# 2_waffling60-MXHS-ISO_matrix.net
KiCad netlist of a schematic drawn in Altium Designer
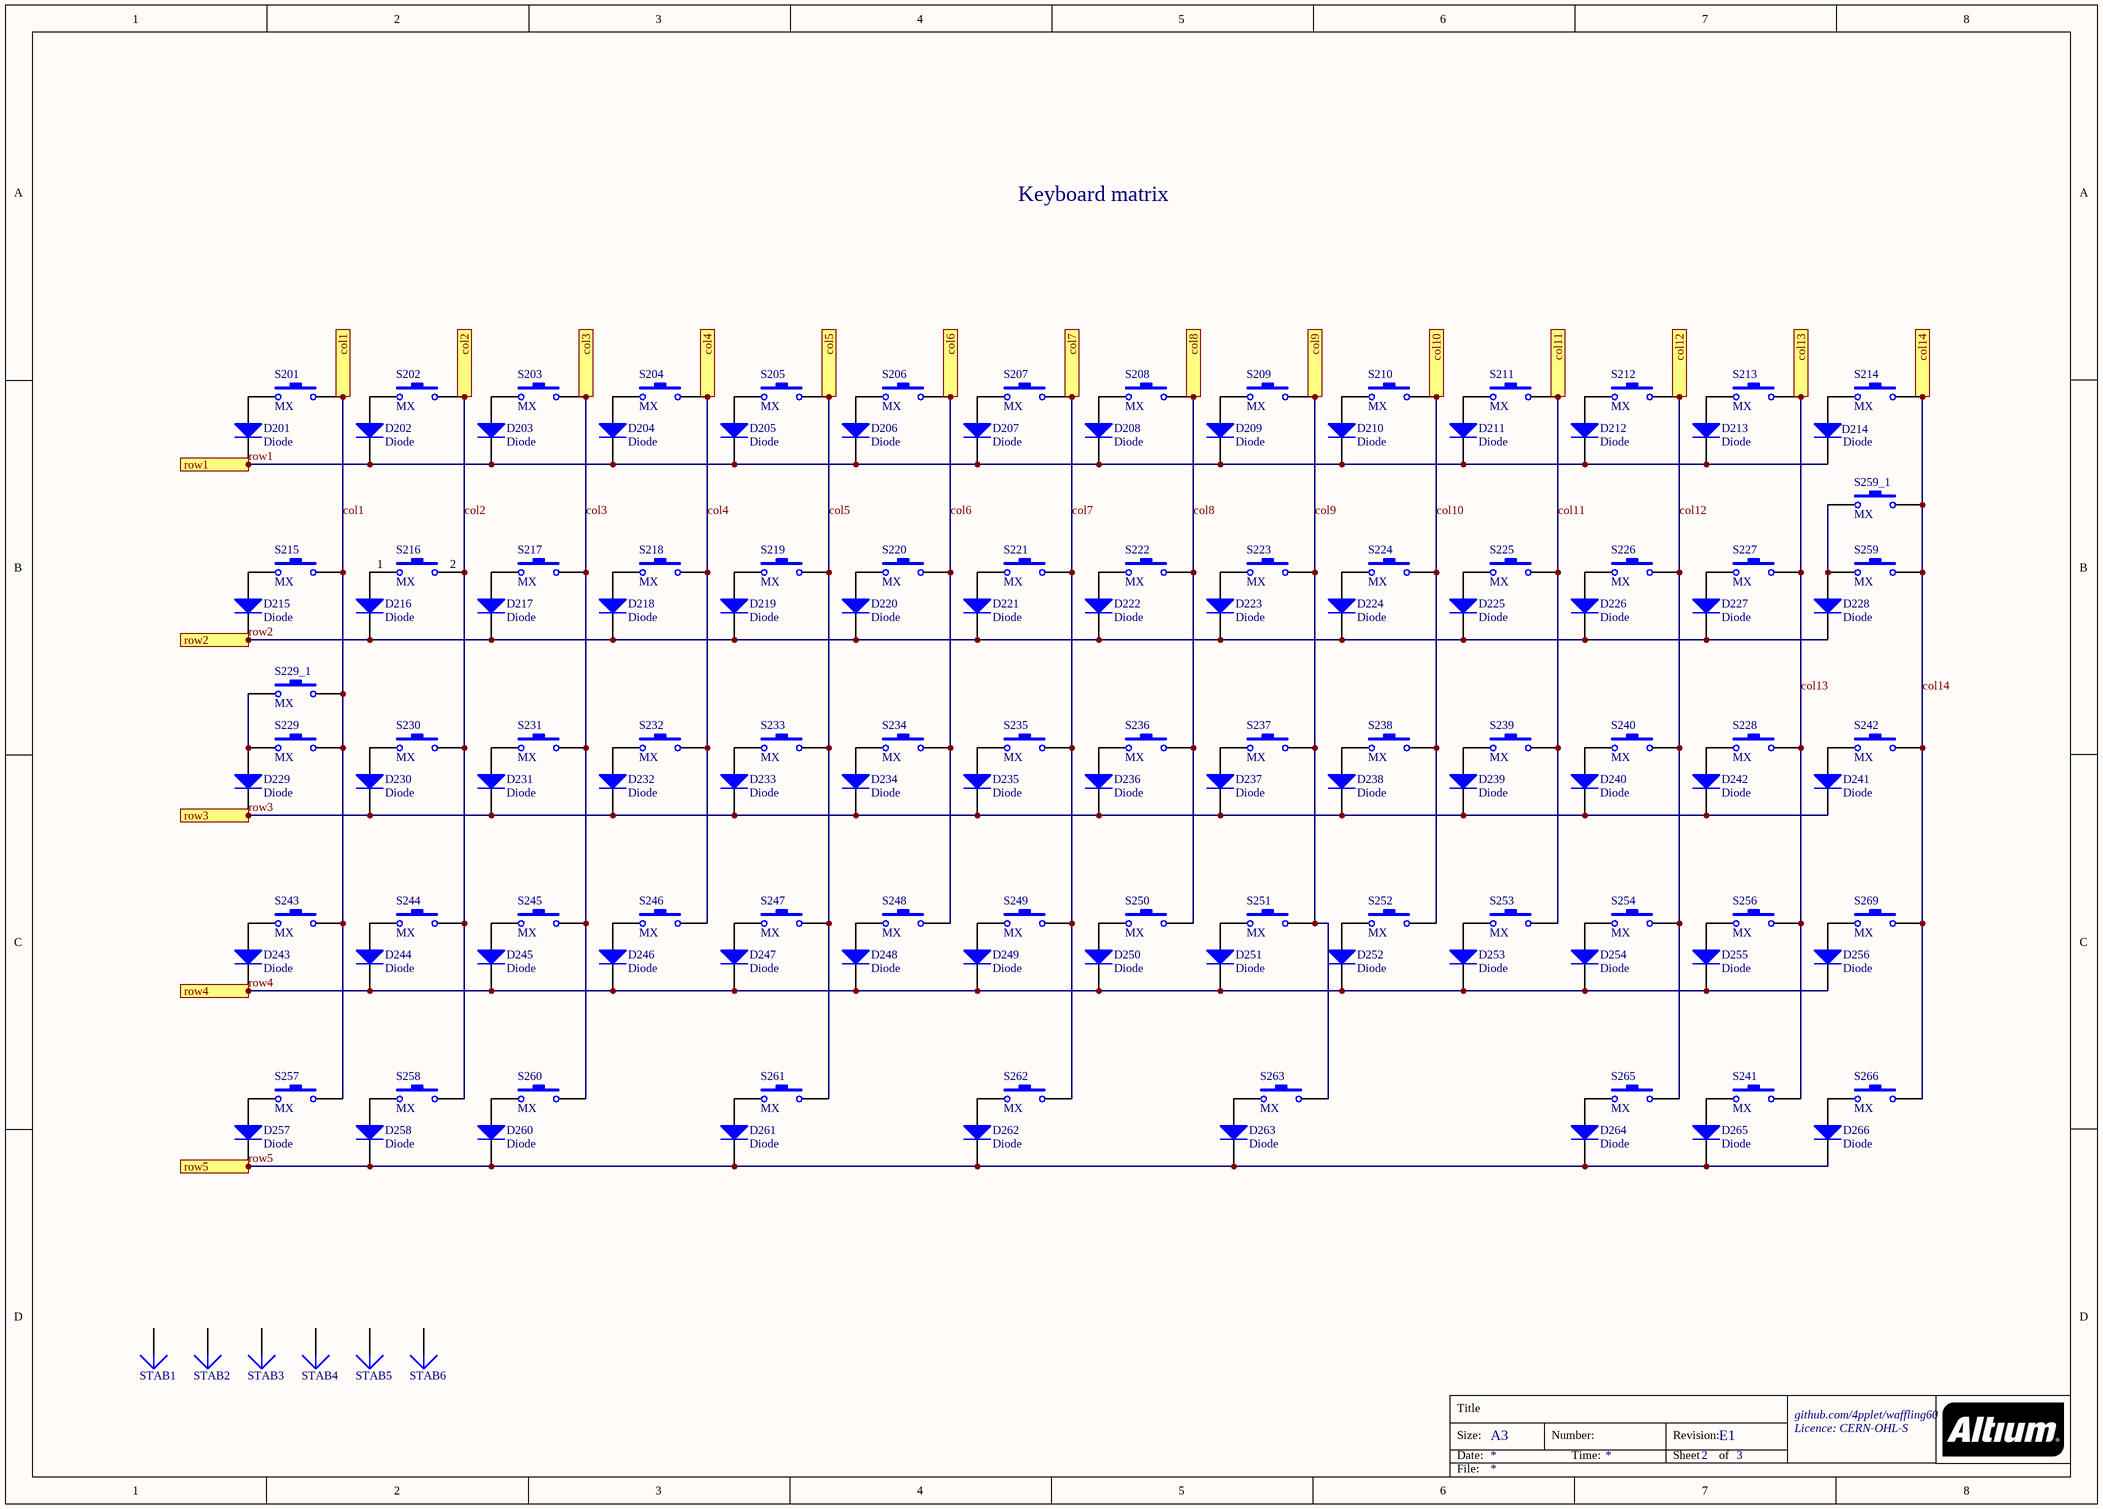
[diagram p0: 2_waffling60-MXHS-ISO_matrix.SchDoc]

(export (version "E")
  (design (tool "Eeschema 10.0.6"))
  (components
    (comp (ref "D201")
      (value "Diode")
      (footprint "SOD-123")
      (description "Default Diode")
      (fields (field (name "LCSC PART #") "C81598") (field (name "MRF.PART") "1N4148W"))
      (libsource (lib "Miscellaneous Devices") (part "Diode"))
    )
    (comp (ref "D202")
      (value "Diode")
      (footprint "SOD-123")
      (description "Default Diode")
      (fields (field (name "LCSC PART #") "C81598") (field (name "MRF.PART") "1N4148W"))
      (libsource (lib "Miscellaneous Devices") (part "Diode"))
    )
    (comp (ref "D203")
      (value "Diode")
      (footprint "SOD-123")
      (description "Default Diode")
      (fields (field (name "LCSC PART #") "C81598") (field (name "MRF.PART") "1N4148W"))
      (libsource (lib "Miscellaneous Devices") (part "Diode"))
    )
    (comp (ref "D204")
      (value "Diode")
      (footprint "SOD-123")
      (description "Default Diode")
      (fields (field (name "LCSC PART #") "C81598") (field (name "MRF.PART") "1N4148W"))
      (libsource (lib "Miscellaneous Devices") (part "Diode"))
    )
    (comp (ref "D205")
      (value "Diode")
      (footprint "SOD-123")
      (description "Default Diode")
      (fields (field (name "LCSC PART #") "C81598") (field (name "MRF.PART") "1N4148W"))
      (libsource (lib "Miscellaneous Devices") (part "Diode"))
    )
    (comp (ref "D206")
      (value "Diode")
      (footprint "SOD-123")
      (description "Default Diode")
      (fields (field (name "LCSC PART #") "C81598") (field (name "MRF.PART") "1N4148W"))
      (libsource (lib "Miscellaneous Devices") (part "Diode"))
    )
    (comp (ref "D207")
      (value "Diode")
      (footprint "SOD-123")
      (description "Default Diode")
      (fields (field (name "LCSC PART #") "C81598") (field (name "MRF.PART") "1N4148W"))
      (libsource (lib "Miscellaneous Devices") (part "Diode"))
    )
    (comp (ref "D208")
      (value "Diode")
      (footprint "SOD-123")
      (description "Default Diode")
      (fields (field (name "LCSC PART #") "C81598") (field (name "MRF.PART") "1N4148W"))
      (libsource (lib "Miscellaneous Devices") (part "Diode"))
    )
    (comp (ref "D209")
      (value "Diode")
      (footprint "SOD-123")
      (description "Default Diode")
      (fields (field (name "LCSC PART #") "C81598") (field (name "MRF.PART") "1N4148W"))
      (libsource (lib "Miscellaneous Devices") (part "Diode"))
    )
    (comp (ref "D210")
      (value "Diode")
      (footprint "SOD-123")
      (description "Default Diode")
      (fields (field (name "LCSC PART #") "C81598") (field (name "MRF.PART") "1N4148W"))
      (libsource (lib "Miscellaneous Devices") (part "Diode"))
    )
    (comp (ref "D211")
      (value "Diode")
      (footprint "SOD-123")
      (description "Default Diode")
      (fields (field (name "LCSC PART #") "C81598") (field (name "MRF.PART") "1N4148W"))
      (libsource (lib "Miscellaneous Devices") (part "Diode"))
    )
    (comp (ref "D212")
      (value "Diode")
      (footprint "SOD-123")
      (description "Default Diode")
      (fields (field (name "LCSC PART #") "C81598") (field (name "MRF.PART") "1N4148W"))
      (libsource (lib "Miscellaneous Devices") (part "Diode"))
    )
    (comp (ref "D213")
      (value "Diode")
      (footprint "SOD-123")
      (description "Default Diode")
      (fields (field (name "LCSC PART #") "C81598") (field (name "MRF.PART") "1N4148W"))
      (libsource (lib "Miscellaneous Devices") (part "Diode"))
    )
    (comp (ref "D214")
      (value "Diode")
      (footprint "SOD-123")
      (description "Default Diode")
      (fields (field (name "LCSC PART #") "C81598") (field (name "MRF.PART") "1N4148W"))
      (libsource (lib "Miscellaneous Devices") (part "Diode"))
    )
    (comp (ref "D215")
      (value "Diode")
      (footprint "SOD-123")
      (description "Default Diode")
      (fields (field (name "LCSC PART #") "C81598") (field (name "MRF.PART") "1N4148W"))
      (libsource (lib "Miscellaneous Devices") (part "Diode"))
    )
    (comp (ref "D216")
      (value "Diode")
      (footprint "SOD-123")
      (description "Default Diode")
      (fields (field (name "LCSC PART #") "C81598") (field (name "MRF.PART") "1N4148W"))
      (libsource (lib "Miscellaneous Devices") (part "Diode"))
    )
    (comp (ref "D217")
      (value "Diode")
      (footprint "SOD-123")
      (description "Default Diode")
      (fields (field (name "LCSC PART #") "C81598") (field (name "MRF.PART") "1N4148W"))
      (libsource (lib "Miscellaneous Devices") (part "Diode"))
    )
    (comp (ref "D218")
      (value "Diode")
      (footprint "SOD-123")
      (description "Default Diode")
      (fields (field (name "LCSC PART #") "C81598") (field (name "MRF.PART") "1N4148W"))
      (libsource (lib "Miscellaneous Devices") (part "Diode"))
    )
    (comp (ref "D219")
      (value "Diode")
      (footprint "SOD-123")
      (description "Default Diode")
      (fields (field (name "LCSC PART #") "C81598") (field (name "MRF.PART") "1N4148W"))
      (libsource (lib "Miscellaneous Devices") (part "Diode"))
    )
    (comp (ref "D220")
      (value "Diode")
      (footprint "SOD-123")
      (description "Default Diode")
      (fields (field (name "LCSC PART #") "C81598") (field (name "MRF.PART") "1N4148W"))
      (libsource (lib "Miscellaneous Devices") (part "Diode"))
    )
    (comp (ref "D221")
      (value "Diode")
      (footprint "SOD-123")
      (description "Default Diode")
      (fields (field (name "LCSC PART #") "C81598") (field (name "MRF.PART") "1N4148W"))
      (libsource (lib "Miscellaneous Devices") (part "Diode"))
    )
    (comp (ref "D222")
      (value "Diode")
      (footprint "SOD-123")
      (description "Default Diode")
      (fields (field (name "LCSC PART #") "C81598") (field (name "MRF.PART") "1N4148W"))
      (libsource (lib "Miscellaneous Devices") (part "Diode"))
    )
    (comp (ref "D223")
      (value "Diode")
      (footprint "SOD-123")
      (description "Default Diode")
      (fields (field (name "LCSC PART #") "C81598") (field (name "MRF.PART") "1N4148W"))
      (libsource (lib "Miscellaneous Devices") (part "Diode"))
    )
    (comp (ref "D224")
      (value "Diode")
      (footprint "SOD-123")
      (description "Default Diode")
      (fields (field (name "LCSC PART #") "C81598") (field (name "MRF.PART") "1N4148W"))
      (libsource (lib "Miscellaneous Devices") (part "Diode"))
    )
    (comp (ref "D225")
      (value "Diode")
      (footprint "SOD-123")
      (description "Default Diode")
      (fields (field (name "LCSC PART #") "C81598") (field (name "MRF.PART") "1N4148W"))
      (libsource (lib "Miscellaneous Devices") (part "Diode"))
    )
    (comp (ref "D226")
      (value "Diode")
      (footprint "SOD-123")
      (description "Default Diode")
      (fields (field (name "LCSC PART #") "C81598") (field (name "MRF.PART") "1N4148W"))
      (libsource (lib "Miscellaneous Devices") (part "Diode"))
    )
    (comp (ref "D227")
      (value "Diode")
      (footprint "SOD-123")
      (description "Default Diode")
      (fields (field (name "LCSC PART #") "C81598") (field (name "MRF.PART") "1N4148W"))
      (libsource (lib "Miscellaneous Devices") (part "Diode"))
    )
    (comp (ref "D228")
      (value "Diode")
      (footprint "SOD-123")
      (description "Default Diode")
      (fields (field (name "LCSC PART #") "C81598") (field (name "MRF.PART") "1N4148W"))
      (libsource (lib "Miscellaneous Devices") (part "Diode"))
    )
    (comp (ref "D229")
      (value "Diode")
      (footprint "SOD-123")
      (description "Default Diode")
      (fields (field (name "LCSC PART #") "C81598") (field (name "MRF.PART") "1N4148W"))
      (libsource (lib "Miscellaneous Devices") (part "Diode"))
    )
    (comp (ref "D230")
      (value "Diode")
      (footprint "SOD-123")
      (description "Default Diode")
      (fields (field (name "LCSC PART #") "C81598") (field (name "MRF.PART") "1N4148W"))
      (libsource (lib "Miscellaneous Devices") (part "Diode"))
    )
    (comp (ref "D231")
      (value "Diode")
      (footprint "SOD-123")
      (description "Default Diode")
      (fields (field (name "LCSC PART #") "C81598") (field (name "MRF.PART") "1N4148W"))
      (libsource (lib "Miscellaneous Devices") (part "Diode"))
    )
    (comp (ref "D232")
      (value "Diode")
      (footprint "SOD-123")
      (description "Default Diode")
      (fields (field (name "LCSC PART #") "C81598") (field (name "MRF.PART") "1N4148W"))
      (libsource (lib "Miscellaneous Devices") (part "Diode"))
    )
    (comp (ref "D233")
      (value "Diode")
      (footprint "SOD-123")
      (description "Default Diode")
      (fields (field (name "LCSC PART #") "C81598") (field (name "MRF.PART") "1N4148W"))
      (libsource (lib "Miscellaneous Devices") (part "Diode"))
    )
    (comp (ref "D234")
      (value "Diode")
      (footprint "SOD-123")
      (description "Default Diode")
      (fields (field (name "LCSC PART #") "C81598") (field (name "MRF.PART") "1N4148W"))
      (libsource (lib "Miscellaneous Devices") (part "Diode"))
    )
    (comp (ref "D235")
      (value "Diode")
      (footprint "SOD-123")
      (description "Default Diode")
      (fields (field (name "LCSC PART #") "C81598") (field (name "MRF.PART") "1N4148W"))
      (libsource (lib "Miscellaneous Devices") (part "Diode"))
    )
    (comp (ref "D236")
      (value "Diode")
      (footprint "SOD-123")
      (description "Default Diode")
      (fields (field (name "LCSC PART #") "C81598") (field (name "MRF.PART") "1N4148W"))
      (libsource (lib "Miscellaneous Devices") (part "Diode"))
    )
    (comp (ref "D237")
      (value "Diode")
      (footprint "SOD-123")
      (description "Default Diode")
      (fields (field (name "LCSC PART #") "C81598") (field (name "MRF.PART") "1N4148W"))
      (libsource (lib "Miscellaneous Devices") (part "Diode"))
    )
    (comp (ref "D238")
      (value "Diode")
      (footprint "SOD-123")
      (description "Default Diode")
      (fields (field (name "LCSC PART #") "C81598") (field (name "MRF.PART") "1N4148W"))
      (libsource (lib "Miscellaneous Devices") (part "Diode"))
    )
    (comp (ref "D239")
      (value "Diode")
      (footprint "SOD-123")
      (description "Default Diode")
      (fields (field (name "LCSC PART #") "C81598") (field (name "MRF.PART") "1N4148W"))
      (libsource (lib "Miscellaneous Devices") (part "Diode"))
    )
    (comp (ref "D240")
      (value "Diode")
      (footprint "SOD-123")
      (description "Default Diode")
      (fields (field (name "LCSC PART #") "C81598") (field (name "MRF.PART") "1N4148W"))
      (libsource (lib "Miscellaneous Devices") (part "Diode"))
    )
    (comp (ref "D241")
      (value "Diode")
      (footprint "SOD-123")
      (description "Default Diode")
      (fields (field (name "LCSC PART #") "C81598") (field (name "MRF.PART") "1N4148W"))
      (libsource (lib "Miscellaneous Devices") (part "Diode"))
    )
    (comp (ref "D242")
      (value "Diode")
      (footprint "SOD-123")
      (description "Default Diode")
      (fields (field (name "LCSC PART #") "C81598") (field (name "MRF.PART") "1N4148W"))
      (libsource (lib "Miscellaneous Devices") (part "Diode"))
    )
    (comp (ref "D243")
      (value "Diode")
      (footprint "SOD-123")
      (description "Default Diode")
      (fields (field (name "LCSC PART #") "C81598") (field (name "MRF.PART") "1N4148W"))
      (libsource (lib "Miscellaneous Devices") (part "Diode"))
    )
    (comp (ref "D244")
      (value "Diode")
      (footprint "SOD-123")
      (description "Default Diode")
      (fields (field (name "LCSC PART #") "C81598") (field (name "MRF.PART") "1N4148W"))
      (libsource (lib "Miscellaneous Devices") (part "Diode"))
    )
    (comp (ref "D245")
      (value "Diode")
      (footprint "SOD-123")
      (description "Default Diode")
      (fields (field (name "LCSC PART #") "C81598") (field (name "MRF.PART") "1N4148W"))
      (libsource (lib "Miscellaneous Devices") (part "Diode"))
    )
    (comp (ref "D246")
      (value "Diode")
      (footprint "SOD-123")
      (description "Default Diode")
      (fields (field (name "LCSC PART #") "C81598") (field (name "MRF.PART") "1N4148W"))
      (libsource (lib "Miscellaneous Devices") (part "Diode"))
    )
    (comp (ref "D247")
      (value "Diode")
      (footprint "SOD-123")
      (description "Default Diode")
      (fields (field (name "LCSC PART #") "C81598") (field (name "MRF.PART") "1N4148W"))
      (libsource (lib "Miscellaneous Devices") (part "Diode"))
    )
    (comp (ref "D248")
      (value "Diode")
      (footprint "SOD-123")
      (description "Default Diode")
      (fields (field (name "LCSC PART #") "C81598") (field (name "MRF.PART") "1N4148W"))
      (libsource (lib "Miscellaneous Devices") (part "Diode"))
    )
    (comp (ref "D249")
      (value "Diode")
      (footprint "SOD-123")
      (description "Default Diode")
      (fields (field (name "LCSC PART #") "C81598") (field (name "MRF.PART") "1N4148W"))
      (libsource (lib "Miscellaneous Devices") (part "Diode"))
    )
    (comp (ref "D250")
      (value "Diode")
      (footprint "SOD-123")
      (description "Default Diode")
      (fields (field (name "LCSC PART #") "C81598") (field (name "MRF.PART") "1N4148W"))
      (libsource (lib "Miscellaneous Devices") (part "Diode"))
    )
    (comp (ref "D251")
      (value "Diode")
      (footprint "SOD-123")
      (description "Default Diode")
      (fields (field (name "LCSC PART #") "C81598") (field (name "MRF.PART") "1N4148W"))
      (libsource (lib "Miscellaneous Devices") (part "Diode"))
    )
    (comp (ref "D252")
      (value "Diode")
      (footprint "SOD-123")
      (description "Default Diode")
      (fields (field (name "LCSC PART #") "C81598") (field (name "MRF.PART") "1N4148W"))
      (libsource (lib "Miscellaneous Devices") (part "Diode"))
    )
    (comp (ref "D253")
      (value "Diode")
      (footprint "SOD-123")
      (description "Default Diode")
      (fields (field (name "LCSC PART #") "C81598") (field (name "MRF.PART") "1N4148W"))
      (libsource (lib "Miscellaneous Devices") (part "Diode"))
    )
    (comp (ref "D254")
      (value "Diode")
      (footprint "SOD-123")
      (description "Default Diode")
      (fields (field (name "LCSC PART #") "C81598") (field (name "MRF.PART") "1N4148W"))
      (libsource (lib "Miscellaneous Devices") (part "Diode"))
    )
    (comp (ref "D255")
      (value "Diode")
      (footprint "SOD-123")
      (description "Default Diode")
      (fields (field (name "LCSC PART #") "C81598") (field (name "MRF.PART") "1N4148W"))
      (libsource (lib "Miscellaneous Devices") (part "Diode"))
    )
    (comp (ref "D256")
      (value "Diode")
      (footprint "SOD-123")
      (description "Default Diode")
      (fields (field (name "LCSC PART #") "C81598") (field (name "MRF.PART") "1N4148W"))
      (libsource (lib "Miscellaneous Devices") (part "Diode"))
    )
    (comp (ref "D257")
      (value "Diode")
      (footprint "SOD-123")
      (description "Default Diode")
      (fields (field (name "LCSC PART #") "C81598") (field (name "MRF.PART") "1N4148W"))
      (libsource (lib "Miscellaneous Devices") (part "Diode"))
    )
    (comp (ref "D258")
      (value "Diode")
      (footprint "SOD-123")
      (description "Default Diode")
      (fields (field (name "LCSC PART #") "C81598") (field (name "MRF.PART") "1N4148W"))
      (libsource (lib "Miscellaneous Devices") (part "Diode"))
    )
    (comp (ref "D260")
      (value "Diode")
      (footprint "SOD-123")
      (description "Default Diode")
      (fields (field (name "LCSC PART #") "C81598") (field (name "MRF.PART") "1N4148W"))
      (libsource (lib "Miscellaneous Devices") (part "Diode"))
    )
    (comp (ref "D261")
      (value "Diode")
      (footprint "SOD-123")
      (description "Default Diode")
      (fields (field (name "LCSC PART #") "C81598") (field (name "MRF.PART") "1N4148W"))
      (libsource (lib "Miscellaneous Devices") (part "Diode"))
    )
    (comp (ref "D262")
      (value "Diode")
      (footprint "SOD-123")
      (description "Default Diode")
      (fields (field (name "LCSC PART #") "C81598") (field (name "MRF.PART") "1N4148W"))
      (libsource (lib "Miscellaneous Devices") (part "Diode"))
    )
    (comp (ref "D263")
      (value "Diode")
      (footprint "SOD-123")
      (description "Default Diode")
      (fields (field (name "LCSC PART #") "C81598") (field (name "MRF.PART") "1N4148W"))
      (libsource (lib "Miscellaneous Devices") (part "Diode"))
    )
    (comp (ref "D264")
      (value "Diode")
      (footprint "SOD-123")
      (description "Default Diode")
      (fields (field (name "LCSC PART #") "C81598") (field (name "MRF.PART") "1N4148W"))
      (libsource (lib "Miscellaneous Devices") (part "Diode"))
    )
    (comp (ref "D265")
      (value "Diode")
      (footprint "SOD-123")
      (description "Default Diode")
      (fields (field (name "LCSC PART #") "C81598") (field (name "MRF.PART") "1N4148W"))
      (libsource (lib "Miscellaneous Devices") (part "Diode"))
    )
    (comp (ref "D266")
      (value "Diode")
      (footprint "SOD-123")
      (description "Default Diode")
      (fields (field (name "LCSC PART #") "C81598") (field (name "MRF.PART") "1N4148W"))
      (libsource (lib "Miscellaneous Devices") (part "Diode"))
    )
    (comp (ref "S201")
      (value "MX")
      (footprint "MXHS-switch - 1U Top layer - AS2")
      (description "Switch")
      (fields (field (name "LCSC PART #") "C5156480") (field (name "MRF.PART") "CPG151101S11-16"))
      (libsource (lib "Miscellaneous Devices") (part "SW-PB"))
    )
    (comp (ref "S202")
      (value "MX")
      (footprint "MXHS-switch - 1U Top layer - switched pol AS2")
      (description "Switch")
      (fields (field (name "LCSC PART #") "C5156480") (field (name "MRF.PART") "CPG151101S11-16"))
      (libsource (lib "Miscellaneous Devices") (part "SW-PB"))
    )
    (comp (ref "S203")
      (value "MX")
      (footprint "MXHS-switch - 1U Top layer - AS2")
      (description "Switch")
      (fields (field (name "LCSC PART #") "C5156480") (field (name "MRF.PART") "CPG151101S11-16"))
      (libsource (lib "Miscellaneous Devices") (part "SW-PB"))
    )
    (comp (ref "S204")
      (value "MX")
      (footprint "MXHS-switch - 1U Top layer - switched pol AS2")
      (description "Switch")
      (fields (field (name "LCSC PART #") "C5156480") (field (name "MRF.PART") "CPG151101S11-16"))
      (libsource (lib "Miscellaneous Devices") (part "SW-PB"))
    )
    (comp (ref "S205")
      (value "MX")
      (footprint "MXHS-switch - 1U Top layer - AS2")
      (description "Switch")
      (fields (field (name "LCSC PART #") "C5156480") (field (name "MRF.PART") "CPG151101S11-16"))
      (libsource (lib "Miscellaneous Devices") (part "SW-PB"))
    )
    (comp (ref "S206")
      (value "MX")
      (footprint "MXHS-switch - 1U Top layer - AS2")
      (description "Switch")
      (fields (field (name "LCSC PART #") "C5156480") (field (name "MRF.PART") "CPG151101S11-16"))
      (libsource (lib "Miscellaneous Devices") (part "SW-PB"))
    )
    (comp (ref "S207")
      (value "MX")
      (footprint "MXHS-switch - 1U Top layer - AS2")
      (description "Switch")
      (fields (field (name "LCSC PART #") "C5156480") (field (name "MRF.PART") "CPG151101S11-16"))
      (libsource (lib "Miscellaneous Devices") (part "SW-PB"))
    )
    (comp (ref "S208")
      (value "MX")
      (footprint "MXHS-switch - 1U Top layer - AS2")
      (description "Switch")
      (fields (field (name "LCSC PART #") "C5156480") (field (name "MRF.PART") "CPG151101S11-16"))
      (libsource (lib "Miscellaneous Devices") (part "SW-PB"))
    )
    (comp (ref "S209")
      (value "MX")
      (footprint "MXHS-switch - 1U Top layer - AS2")
      (description "Switch")
      (fields (field (name "LCSC PART #") "C5156480") (field (name "MRF.PART") "CPG151101S11-16"))
      (libsource (lib "Miscellaneous Devices") (part "SW-PB"))
    )
    (comp (ref "S210")
      (value "MX")
      (footprint "MXHS-switch - 1U Top layer - AS2")
      (description "Switch")
      (fields (field (name "LCSC PART #") "C5156480") (field (name "MRF.PART") "CPG151101S11-16"))
      (libsource (lib "Miscellaneous Devices") (part "SW-PB"))
    )
    (comp (ref "S211")
      (value "MX")
      (footprint "MXHS-switch - 1U Top layer - switched pol AS2")
      (description "Switch")
      (fields (field (name "LCSC PART #") "C5156480") (field (name "MRF.PART") "CPG151101S11-16"))
      (libsource (lib "Miscellaneous Devices") (part "SW-PB"))
    )
    (comp (ref "S212")
      (value "MX")
      (footprint "MXHS-switch - 1U Top layer - AS2")
      (description "Switch")
      (fields (field (name "LCSC PART #") "C5156480") (field (name "MRF.PART") "CPG151101S11-16"))
      (libsource (lib "Miscellaneous Devices") (part "SW-PB"))
    )
    (comp (ref "S213")
      (value "MX")
      (footprint "MXHS-switch - 1U Top layer - AS2")
      (description "Switch")
      (fields (field (name "LCSC PART #") "C5156480") (field (name "MRF.PART") "CPG151101S11-16"))
      (libsource (lib "Miscellaneous Devices") (part "SW-PB"))
    )
    (comp (ref "S214")
      (value "MX")
      (footprint "MXHS-switch - 1U Top layer - AS2 - S2")
      (description "Switch")
      (fields (field (name "LCSC PART #") "C5156480") (field (name "MRF.PART") "CPG151101S11-16"))
      (libsource (lib "Miscellaneous Devices") (part "SW-PB"))
    )
    (comp (ref "S215")
      (value "MX")
      (footprint "MXHS-switch - 1U Top layer - AS2")
      (description "TAB")
      (fields (field (name "LCSC PART #") "C5156480") (field (name "MRF.PART") "CPG151101S11-16"))
      (libsource (lib "Miscellaneous Devices") (part "SW-PB"))
    )
    (comp (ref "S216")
      (value "MX")
      (footprint "MXHS-switch - 1U Top layer - switched pol AS2")
      (description "Switch")
      (fields (field (name "LCSC PART #") "C5156480") (field (name "MRF.PART") "CPG151101S11-16"))
      (libsource (lib "") (part "SW-PB_1"))
    )
    (comp (ref "S217")
      (value "MX")
      (footprint "MXHS-switch - 1U Top layer - AS2")
      (description "Switch")
      (fields (field (name "LCSC PART #") "C5156480") (field (name "MRF.PART") "CPG151101S11-16"))
      (libsource (lib "Miscellaneous Devices") (part "SW-PB"))
    )
    (comp (ref "S218")
      (value "MX")
      (footprint "MXHS-switch - 1U Top layer - AS2")
      (description "Switch")
      (fields (field (name "LCSC PART #") "C5156480") (field (name "MRF.PART") "CPG151101S11-16"))
      (libsource (lib "Miscellaneous Devices") (part "SW-PB"))
    )
    (comp (ref "S219")
      (value "MX")
      (footprint "MXHS-switch - 1U Top layer - AS2")
      (description "Switch")
      (fields (field (name "LCSC PART #") "C5156480") (field (name "MRF.PART") "CPG151101S11-16"))
      (libsource (lib "Miscellaneous Devices") (part "SW-PB"))
    )
    (comp (ref "S220")
      (value "MX")
      (footprint "MXHS-switch - 1U Top layer - switched pol AS2")
      (description "Switch")
      (fields (field (name "LCSC PART #") "C5156480") (field (name "MRF.PART") "CPG151101S11-16"))
      (libsource (lib "Miscellaneous Devices") (part "SW-PB"))
    )
    (comp (ref "S221")
      (value "MX")
      (footprint "MXHS-switch - 1U Top layer - AS2")
      (description "Switch")
      (fields (field (name "LCSC PART #") "C5156480") (field (name "MRF.PART") "CPG151101S11-16"))
      (libsource (lib "Miscellaneous Devices") (part "SW-PB"))
    )
    (comp (ref "S222")
      (value "MX")
      (footprint "MXHS-switch - 1U Top layer - switched pol AS2")
      (description "Switch")
      (fields (field (name "LCSC PART #") "C5156480") (field (name "MRF.PART") "CPG151101S11-16"))
      (libsource (lib "Miscellaneous Devices") (part "SW-PB"))
    )
    (comp (ref "S223")
      (value "MX")
      (footprint "MXHS-switch - 1U Top layer - AS2")
      (description "Switch")
      (fields (field (name "LCSC PART #") "C5156480") (field (name "MRF.PART") "CPG151101S11-16"))
      (libsource (lib "Miscellaneous Devices") (part "SW-PB"))
    )
    (comp (ref "S224")
      (value "MX")
      (footprint "MXHS-switch - 1U Top layer - AS2")
      (description "Switch")
      (fields (field (name "LCSC PART #") "C5156480") (field (name "MRF.PART") "CPG151101S11-16"))
      (libsource (lib "Miscellaneous Devices") (part "SW-PB"))
    )
    (comp (ref "S225")
      (value "MX")
      (footprint "MXHS-switch - 1U Top layer - AS2")
      (description "Switch")
      (fields (field (name "LCSC PART #") "C5156480") (field (name "MRF.PART") "CPG151101S11-16"))
      (libsource (lib "Miscellaneous Devices") (part "SW-PB"))
    )
    (comp (ref "S226")
      (value "MX")
      (footprint "MXHS-switch - 1U Top layer - AS2")
      (description "Switch")
      (fields (field (name "LCSC PART #") "C5156480") (field (name "MRF.PART") "CPG151101S11-16"))
      (libsource (lib "Miscellaneous Devices") (part "SW-PB"))
    )
    (comp (ref "S227")
      (value "MX")
      (footprint "MXHS-switch - 1U Top layer - switched pol AS2")
      (description "Switch")
      (fields (field (name "LCSC PART #") "C5156480") (field (name "MRF.PART") "CPG151101S11-16"))
      (libsource (lib "Miscellaneous Devices") (part "SW-PB"))
    )
    (comp (ref "S228")
      (value "MX")
      (footprint "MXHS-switch - 1U Top layer - switched pol AS2")
      (description "Switch")
      (fields (field (name "LCSC PART #") "C5156480") (field (name "MRF.PART") "CPG151101S11-16"))
      (libsource (lib "Miscellaneous Devices") (part "SW-PB"))
    )
    (comp (ref "S229")
      (value "MX")
      (footprint "MXHS-switch - 1U Top layer - AS2")
      (description "Switch")
      (fields (field (name "LCSC PART #") "C5156480") (field (name "MRF.PART") "CPG151101S11-16"))
      (libsource (lib "Miscellaneous Devices") (part "SW-PB"))
    )
    (comp (ref "S229_1")
      (value "MX")
      (footprint "MXHS-switch - 1U Top layer - AS2")
      (description "Switch")
      (fields (field (name "LCSC PART #") "C5156480") (field (name "MRF.PART") "CPG151101S11-16"))
      (libsource (lib "Miscellaneous Devices") (part "SW-PB"))
    )
    (comp (ref "S230")
      (value "MX")
      (footprint "MXHS-switch - 1U Top layer - switched pol AS2")
      (description "Switch")
      (fields (field (name "LCSC PART #") "C5156480") (field (name "MRF.PART") "CPG151101S11-16"))
      (libsource (lib "Miscellaneous Devices") (part "SW-PB"))
    )
    (comp (ref "S231")
      (value "MX")
      (footprint "MXHS-switch - 1U Top layer - AS2")
      (description "Switch")
      (fields (field (name "LCSC PART #") "C5156480") (field (name "MRF.PART") "CPG151101S11-16"))
      (libsource (lib "Miscellaneous Devices") (part "SW-PB"))
    )
    (comp (ref "S232")
      (value "MX")
      (footprint "MXHS-switch - 1U Top layer - AS2")
      (description "Switch")
      (fields (field (name "LCSC PART #") "C5156480") (field (name "MRF.PART") "CPG151101S11-16"))
      (libsource (lib "Miscellaneous Devices") (part "SW-PB"))
    )
    (comp (ref "S233")
      (value "MX")
      (footprint "MXHS-switch - 1U Top layer - AS2")
      (description "Switch")
      (fields (field (name "LCSC PART #") "C5156480") (field (name "MRF.PART") "CPG151101S11-16"))
      (libsource (lib "Miscellaneous Devices") (part "SW-PB"))
    )
    (comp (ref "S234")
      (value "MX")
      (footprint "MXHS-switch - 1U Top layer - switched pol AS2")
      (description "Switch")
      (fields (field (name "LCSC PART #") "C5156480") (field (name "MRF.PART") "CPG151101S11-16"))
      (libsource (lib "Miscellaneous Devices") (part "SW-PB"))
    )
    (comp (ref "S235")
      (value "MX")
      (footprint "MXHS-switch - 1U Top layer - AS2 - S2")
      (description "Switch")
      (fields (field (name "LCSC PART #") "C5156480") (field (name "MRF.PART") "CPG151101S11-16"))
      (libsource (lib "Miscellaneous Devices") (part "SW-PB"))
    )
    (comp (ref "S236")
      (value "MX")
      (footprint "MXHS-switch - 1U Top layer - AS2")
      (description "Switch")
      (fields (field (name "LCSC PART #") "C5156480") (field (name "MRF.PART") "CPG151101S11-16"))
      (libsource (lib "Miscellaneous Devices") (part "SW-PB"))
    )
    (comp (ref "S237")
      (value "MX")
      (footprint "MXHS-switch - 1U Top layer - AS2")
      (description "Switch")
      (fields (field (name "LCSC PART #") "C5156480") (field (name "MRF.PART") "CPG151101S11-16"))
      (libsource (lib "Miscellaneous Devices") (part "SW-PB"))
    )
    (comp (ref "S238")
      (value "MX")
      (footprint "MXHS-switch - 1U Top layer - AS2")
      (description "Switch")
      (fields (field (name "LCSC PART #") "C5156480") (field (name "MRF.PART") "CPG151101S11-16"))
      (libsource (lib "Miscellaneous Devices") (part "SW-PB"))
    )
    (comp (ref "S239")
      (value "MX")
      (footprint "MXHS-switch - 1U Top layer - AS2")
      (description "Switch")
      (fields (field (name "LCSC PART #") "C5156480") (field (name "MRF.PART") "CPG151101S11-16"))
      (libsource (lib "Miscellaneous Devices") (part "SW-PB"))
    )
    (comp (ref "S240")
      (value "MX")
      (footprint "MXHS-switch - 1U Top layer - AS2")
      (description "Switch")
      (fields (field (name "LCSC PART #") "C5156480") (field (name "MRF.PART") "CPG151101S11-16"))
      (libsource (lib "Miscellaneous Devices") (part "SW-PB"))
    )
    (comp (ref "S241")
      (value "MX")
      (footprint "MXHS-switch - 1U Top layer - AS2")
      (description "Switch")
      (fields (field (name "LCSC PART #") "C5156480") (field (name "MRF.PART") "CPG151101S11-16"))
      (libsource (lib "Miscellaneous Devices") (part "SW-PB"))
    )
    (comp (ref "S242")
      (value "MX")
      (footprint "MXHS-switch - 1U Top layer - switched pol AS2")
      (description "Switch")
      (fields (field (name "LCSC PART #") "C5156480") (field (name "MRF.PART") "CPG151101S11-16"))
      (libsource (lib "Miscellaneous Devices") (part "SW-PB"))
    )
    (comp (ref "S243")
      (value "MX")
      (footprint "MXHS-switch - 1U Top layer - AS2")
      (description "Switch")
      (fields (field (name "LCSC PART #") "C5156480") (field (name "MRF.PART") "CPG151101S11-16"))
      (libsource (lib "Miscellaneous Devices") (part "SW-PB"))
    )
    (comp (ref "S244")
      (value "MX")
      (footprint "MXHS-switch - 1U Top layer - switched pol AS2")
      (description "Switch")
      (fields (field (name "LCSC PART #") "C5156480") (field (name "MRF.PART") "CPG151101S11-16"))
      (libsource (lib "Miscellaneous Devices") (part "SW-PB"))
    )
    (comp (ref "S245")
      (value "MX")
      (footprint "MXHS-switch - 1U Top layer - AS2")
      (description "Switch")
      (fields (field (name "LCSC PART #") "C5156480") (field (name "MRF.PART") "CPG151101S11-16"))
      (libsource (lib "Miscellaneous Devices") (part "SW-PB"))
    )
    (comp (ref "S246")
      (value "MX")
      (footprint "MXHS-switch - 1U Top layer - AS2")
      (description "Switch")
      (fields (field (name "LCSC PART #") "C5156480") (field (name "MRF.PART") "CPG151101S11-16"))
      (libsource (lib "Miscellaneous Devices") (part "SW-PB"))
    )
    (comp (ref "S247")
      (value "MX")
      (footprint "MXHS-switch - 1U Top layer - AS2")
      (description "Switch")
      (fields (field (name "LCSC PART #") "C5156480") (field (name "MRF.PART") "CPG151101S11-16"))
      (libsource (lib "Miscellaneous Devices") (part "SW-PB"))
    )
    (comp (ref "S248")
      (value "MX")
      (footprint "MXHS-switch - 1U Top layer - AS2")
      (description "Switch")
      (fields (field (name "LCSC PART #") "C5156480") (field (name "MRF.PART") "CPG151101S11-16"))
      (libsource (lib "Miscellaneous Devices") (part "SW-PB"))
    )
    (comp (ref "S249")
      (value "MX")
      (footprint "MXHS-switch - 1U Top layer - AS2")
      (description "Switch")
      (fields (field (name "LCSC PART #") "C5156480") (field (name "MRF.PART") "CPG151101S11-16"))
      (libsource (lib "Miscellaneous Devices") (part "SW-PB"))
    )
    (comp (ref "S250")
      (value "MX")
      (footprint "MXHS-switch - 1U Top layer - AS2")
      (description "Switch")
      (fields (field (name "LCSC PART #") "C5156480") (field (name "MRF.PART") "CPG151101S11-16"))
      (libsource (lib "Miscellaneous Devices") (part "SW-PB"))
    )
    (comp (ref "S251")
      (value "MX")
      (footprint "MXHS-switch - 1U Top layer - AS2")
      (description "Switch")
      (fields (field (name "LCSC PART #") "C5156480") (field (name "MRF.PART") "CPG151101S11-16"))
      (libsource (lib "Miscellaneous Devices") (part "SW-PB"))
    )
    (comp (ref "S252")
      (value "MX")
      (footprint "MXHS-switch - 1U Top layer - AS2")
      (description "Switch")
      (fields (field (name "LCSC PART #") "C5156480") (field (name "MRF.PART") "CPG151101S11-16"))
      (libsource (lib "Miscellaneous Devices") (part "SW-PB"))
    )
    (comp (ref "S253")
      (value "MX")
      (footprint "MXHS-switch - 1U Top layer - AS2")
      (description "Switch")
      (fields (field (name "LCSC PART #") "C5156480") (field (name "MRF.PART") "CPG151101S11-16"))
      (libsource (lib "Miscellaneous Devices") (part "SW-PB"))
    )
    (comp (ref "S254")
      (value "MX")
      (footprint "MXHS-switch - 1U Top layer - AS2")
      (description "Switch")
      (fields (field (name "LCSC PART #") "C5156480") (field (name "MRF.PART") "CPG151101S11-16"))
      (libsource (lib "Miscellaneous Devices") (part "SW-PB"))
    )
    (comp (ref "S256")
      (value "MX")
      (footprint "MXHS-switch - 1U Top layer - AS2")
      (description "Switch")
      (fields (field (name "LCSC PART #") "C5156480") (field (name "MRF.PART") "CPG151101S11-16"))
      (libsource (lib "Miscellaneous Devices") (part "SW-PB"))
    )
    (comp (ref "S257")
      (value "MX")
      (footprint "MXHS-switch - 1U Top layer - switched pol AS2")
      (description "Switch")
      (fields (field (name "LCSC PART #") "C5156480") (field (name "MRF.PART") "CPG151101S11-16"))
      (libsource (lib "Miscellaneous Devices") (part "SW-PB"))
    )
    (comp (ref "S258")
      (value "MX")
      (footprint "MXHS-switch - 1U Top layer - AS2")
      (description "Switch")
      (fields (field (name "LCSC PART #") "C5156480") (field (name "MRF.PART") "CPG151101S11-16"))
      (libsource (lib "Miscellaneous Devices") (part "SW-PB"))
    )
    (comp (ref "S259")
      (value "MX")
      (footprint "MXHS-switch - 1U Top layer - AS2 - S2")
      (description "Switch")
      (fields (field (name "LCSC PART #") "C5156480") (field (name "MRF.PART") "CPG151101S11-16"))
      (libsource (lib "Miscellaneous Devices") (part "SW-PB"))
    )
    (comp (ref "S259_1")
      (value "MX")
      (footprint "MXHS-switch - 1U Top layer - AS2 - S1")
      (description "Switch")
      (fields (field (name "LCSC PART #") "C5156480") (field (name "MRF.PART") "CPG151101S11-16"))
      (libsource (lib "Miscellaneous Devices") (part "SW-PB"))
    )
    (comp (ref "S260")
      (value "MX")
      (footprint "MXHS-switch - 1U Top layer - AS2")
      (description "Switch")
      (fields (field (name "LCSC PART #") "C5156480") (field (name "MRF.PART") "CPG151101S11-16"))
      (libsource (lib "Miscellaneous Devices") (part "SW-PB"))
    )
    (comp (ref "S261")
      (value "MX")
      (footprint "MXHS-switch - 1U Top layer - switched pol AS2")
      (description "Switch")
      (fields (field (name "LCSC PART #") "C5156480") (field (name "MRF.PART") "CPG151101S11-16"))
      (libsource (lib "Miscellaneous Devices") (part "SW-PB"))
    )
    (comp (ref "S262")
      (value "MX")
      (footprint "MXHS-switch - 1U Top layer - switched pol AS2")
      (description "Switch")
      (fields (field (name "LCSC PART #") "C5156480") (field (name "MRF.PART") "CPG151101S11-16"))
      (libsource (lib "Miscellaneous Devices") (part "SW-PB"))
    )
    (comp (ref "S263")
      (value "MX")
      (footprint "MXHS-switch - 1U Top layer - switched pol AS2")
      (description "Switch")
      (fields (field (name "LCSC PART #") "C5156480") (field (name "MRF.PART") "CPG151101S11-16"))
      (libsource (lib "Miscellaneous Devices") (part "SW-PB"))
    )
    (comp (ref "S265")
      (value "MX")
      (footprint "MXHS-switch - 1U Top layer - switched pol AS2")
      (description "Switch")
      (fields (field (name "LCSC PART #") "C5156480") (field (name "MRF.PART") "CPG151101S11-16"))
      (libsource (lib "Miscellaneous Devices") (part "SW-PB"))
    )
    (comp (ref "S266")
      (value "MX")
      (footprint "MXHS-switch - 1U Top layer - switched pol AS2")
      (description "Switch")
      (fields (field (name "LCSC PART #") "C5156480") (field (name "MRF.PART") "CPG151101S11-16"))
      (libsource (lib "Miscellaneous Devices") (part "SW-PB"))
    )
    (comp (ref "S269")
      (value "MX")
      (footprint "MXHS-switch - 1U Top layer - AS2")
      (description "Switch")
      (fields (field (name "LCSC PART #") "C5156480") (field (name "MRF.PART") "CPG151101S11-16"))
      (libsource (lib "Miscellaneous Devices") (part "SW-PB"))
    )
    (comp (ref "STAB1")
      (value "Plug")
      (footprint "Stab 2u")
      (libsource (lib "Miscellaneous Connectors") (part "Plug"))
    )
    (comp (ref "STAB2")
      (value "Plug")
      (footprint "Stab 2u")
      (libsource (lib "Miscellaneous Connectors") (part "Plug"))
    )
    (comp (ref "STAB3")
      (value "Plug")
      (footprint "Stab 7U")
      (libsource (lib "Miscellaneous Connectors") (part "Plug"))
    )
    (comp (ref "STAB4")
      (value "Plug")
      (footprint "Stab 10U")
      (libsource (lib "Miscellaneous Connectors") (part "Plug"))
    )
    (comp (ref "STAB5")
      (value "Plug")
      (footprint "Stab 3u")
      (libsource (lib "Miscellaneous Connectors") (part "Plug"))
    )
    (comp (ref "STAB6")
      (value "Plug")
      (footprint "Stab 3u")
      (libsource (lib "Miscellaneous Connectors") (part "Plug"))
    )
  )
  (nets
    (net (code "1") (name "/col1") (class "Default")
      (node (ref "S201") (pin "2") (pinfunction "2_2") (pintype "passive"))
      (node (ref "S215") (pin "2") (pinfunction "2_2") (pintype "passive"))
      (node (ref "S229") (pin "2") (pinfunction "2_2") (pintype "passive"))
      (node (ref "S229_1") (pin "1") (pinfunction "1_1") (pintype "passive"))
      (node (ref "S243") (pin "2") (pinfunction "2_2") (pintype "passive"))
      (node (ref "S257") (pin "1") (pinfunction "1_1") (pintype "passive"))
    )
    (net (code "2") (name "/col2") (class "Default")
      (node (ref "S202") (pin "2") (pinfunction "2_2") (pintype "passive"))
      (node (ref "S216") (pin "2") (pinfunction "2_2") (pintype "passive"))
      (node (ref "S230") (pin "2") (pinfunction "2_2") (pintype "passive"))
      (node (ref "S244") (pin "1") (pinfunction "1_1") (pintype "passive"))
      (node (ref "S258") (pin "2") (pinfunction "2_2") (pintype "passive"))
    )
    (net (code "3") (name "/col3") (class "Default")
      (node (ref "S203") (pin "2") (pinfunction "2_2") (pintype "passive"))
      (node (ref "S217") (pin "2") (pinfunction "2_2") (pintype "passive"))
      (node (ref "S231") (pin "2") (pinfunction "2_2") (pintype "passive"))
      (node (ref "S245") (pin "2") (pinfunction "2_2") (pintype "passive"))
      (node (ref "S260") (pin "2") (pinfunction "2_2") (pintype "passive"))
    )
    (net (code "4") (name "/col4") (class "Default")
      (node (ref "S204") (pin "2") (pinfunction "2_2") (pintype "passive"))
      (node (ref "S218") (pin "2") (pinfunction "2_2") (pintype "passive"))
      (node (ref "S232") (pin "2") (pinfunction "2_2") (pintype "passive"))
      (node (ref "S246") (pin "2") (pinfunction "2_2") (pintype "passive"))
    )
    (net (code "5") (name "/col5") (class "Default")
      (node (ref "S205") (pin "2") (pinfunction "2_2") (pintype "passive"))
      (node (ref "S219") (pin "2") (pinfunction "2_2") (pintype "passive"))
      (node (ref "S233") (pin "2") (pinfunction "2_2") (pintype "passive"))
      (node (ref "S247") (pin "2") (pinfunction "2_2") (pintype "passive"))
      (node (ref "S261") (pin "2") (pinfunction "2_2") (pintype "passive"))
    )
    (net (code "6") (name "/col6") (class "Default")
      (node (ref "S206") (pin "2") (pinfunction "2_2") (pintype "passive"))
      (node (ref "S220") (pin "2") (pinfunction "2_2") (pintype "passive"))
      (node (ref "S234") (pin "2") (pinfunction "2_2") (pintype "passive"))
      (node (ref "S248") (pin "2") (pinfunction "2_2") (pintype "passive"))
    )
    (net (code "7") (name "/col7") (class "Default")
      (node (ref "S207") (pin "2") (pinfunction "2_2") (pintype "passive"))
      (node (ref "S221") (pin "2") (pinfunction "2_2") (pintype "passive"))
      (node (ref "S235") (pin "2") (pinfunction "2_2") (pintype "passive"))
      (node (ref "S249") (pin "2") (pinfunction "2_2") (pintype "passive"))
      (node (ref "S262") (pin "1") (pinfunction "1_1") (pintype "passive"))
    )
    (net (code "8") (name "/col8") (class "Default")
      (node (ref "S208") (pin "2") (pinfunction "2_2") (pintype "passive"))
      (node (ref "S222") (pin "2") (pinfunction "2_2") (pintype "passive"))
      (node (ref "S236") (pin "2") (pinfunction "2_2") (pintype "passive"))
      (node (ref "S250") (pin "2") (pinfunction "2_2") (pintype "passive"))
    )
    (net (code "9") (name "/col9") (class "Default")
      (node (ref "S209") (pin "2") (pinfunction "2_2") (pintype "passive"))
      (node (ref "S223") (pin "2") (pinfunction "2_2") (pintype "passive"))
      (node (ref "S237") (pin "2") (pinfunction "2_2") (pintype "passive"))
      (node (ref "S251") (pin "2") (pinfunction "2_2") (pintype "passive"))
      (node (ref "S263") (pin "2") (pinfunction "2_2") (pintype "passive"))
    )
    (net (code "10") (name "/col10") (class "Default")
      (node (ref "S210") (pin "2") (pinfunction "2_2") (pintype "passive"))
      (node (ref "S224") (pin "2") (pinfunction "2_2") (pintype "passive"))
      (node (ref "S238") (pin "2") (pinfunction "2_2") (pintype "passive"))
      (node (ref "S252") (pin "2") (pinfunction "2_2") (pintype "passive"))
    )
    (net (code "11") (name "/col11") (class "Default")
      (node (ref "S211") (pin "2") (pinfunction "2_2") (pintype "passive"))
      (node (ref "S225") (pin "2") (pinfunction "2_2") (pintype "passive"))
      (node (ref "S239") (pin "2") (pinfunction "2_2") (pintype "passive"))
      (node (ref "S253") (pin "2") (pinfunction "2_2") (pintype "passive"))
    )
    (net (code "12") (name "/col12") (class "Default")
      (node (ref "S212") (pin "2") (pinfunction "2_2") (pintype "passive"))
      (node (ref "S226") (pin "2") (pinfunction "2_2") (pintype "passive"))
      (node (ref "S240") (pin "2") (pinfunction "2_2") (pintype "passive"))
      (node (ref "S254") (pin "2") (pinfunction "2_2") (pintype "passive"))
      (node (ref "S265") (pin "2") (pinfunction "2_2") (pintype "passive"))
    )
    (net (code "13") (name "/col13") (class "Default")
      (node (ref "S213") (pin "2") (pinfunction "2_2") (pintype "passive"))
      (node (ref "S227") (pin "2") (pinfunction "2_2") (pintype "passive"))
      (node (ref "S228") (pin "2") (pinfunction "2_2") (pintype "passive"))
      (node (ref "S241") (pin "1") (pinfunction "1_1") (pintype "passive"))
      (node (ref "S256") (pin "2") (pinfunction "2_2") (pintype "passive"))
    )
    (net (code "14") (name "/col14") (class "Default")
      (node (ref "S214") (pin "1") (pinfunction "1_1") (pintype "passive"))
      (node (ref "S242") (pin "2") (pinfunction "2_2") (pintype "passive"))
      (node (ref "S259") (pin "1") (pinfunction "1_1") (pintype "passive"))
      (node (ref "S259_1") (pin "2") (pinfunction "2_2") (pintype "passive"))
      (node (ref "S266") (pin "2") (pinfunction "2_2") (pintype "passive"))
      (node (ref "S269") (pin "2") (pinfunction "2_2") (pintype "passive"))
    )
    (net (code "15") (name "/row1") (class "Default")
      (node (ref "D201") (pin "2") (pinfunction "K_2") (pintype "passive"))
      (node (ref "D202") (pin "2") (pinfunction "K_2") (pintype "passive"))
      (node (ref "D203") (pin "2") (pinfunction "K_2") (pintype "passive"))
      (node (ref "D204") (pin "2") (pinfunction "K_2") (pintype "passive"))
      (node (ref "D205") (pin "2") (pinfunction "K_2") (pintype "passive"))
      (node (ref "D206") (pin "2") (pinfunction "K_2") (pintype "passive"))
      (node (ref "D207") (pin "2") (pinfunction "K_2") (pintype "passive"))
      (node (ref "D208") (pin "2") (pinfunction "K_2") (pintype "passive"))
      (node (ref "D209") (pin "2") (pinfunction "K_2") (pintype "passive"))
      (node (ref "D210") (pin "2") (pinfunction "K_2") (pintype "passive"))
      (node (ref "D211") (pin "2") (pinfunction "K_2") (pintype "passive"))
      (node (ref "D212") (pin "2") (pinfunction "K_2") (pintype "passive"))
      (node (ref "D213") (pin "2") (pinfunction "K_2") (pintype "passive"))
      (node (ref "D214") (pin "2") (pinfunction "K_2") (pintype "passive"))
    )
    (net (code "16") (name "/row2") (class "Default")
      (node (ref "D215") (pin "2") (pinfunction "K_2") (pintype "passive"))
      (node (ref "D216") (pin "2") (pinfunction "K_2") (pintype "passive"))
      (node (ref "D217") (pin "2") (pinfunction "K_2") (pintype "passive"))
      (node (ref "D218") (pin "2") (pinfunction "K_2") (pintype "passive"))
      (node (ref "D219") (pin "2") (pinfunction "K_2") (pintype "passive"))
      (node (ref "D220") (pin "2") (pinfunction "K_2") (pintype "passive"))
      (node (ref "D221") (pin "2") (pinfunction "K_2") (pintype "passive"))
      (node (ref "D222") (pin "2") (pinfunction "K_2") (pintype "passive"))
      (node (ref "D223") (pin "2") (pinfunction "K_2") (pintype "passive"))
      (node (ref "D224") (pin "2") (pinfunction "K_2") (pintype "passive"))
      (node (ref "D225") (pin "2") (pinfunction "K_2") (pintype "passive"))
      (node (ref "D226") (pin "2") (pinfunction "K_2") (pintype "passive"))
      (node (ref "D227") (pin "2") (pinfunction "K_2") (pintype "passive"))
      (node (ref "D228") (pin "2") (pinfunction "K_2") (pintype "passive"))
    )
    (net (code "17") (name "/row3") (class "Default")
      (node (ref "D229") (pin "2") (pinfunction "K_2") (pintype "passive"))
      (node (ref "D230") (pin "2") (pinfunction "K_2") (pintype "passive"))
      (node (ref "D231") (pin "2") (pinfunction "K_2") (pintype "passive"))
      (node (ref "D232") (pin "2") (pinfunction "K_2") (pintype "passive"))
      (node (ref "D233") (pin "2") (pinfunction "K_2") (pintype "passive"))
      (node (ref "D234") (pin "2") (pinfunction "K_2") (pintype "passive"))
      (node (ref "D235") (pin "2") (pinfunction "K_2") (pintype "passive"))
      (node (ref "D236") (pin "2") (pinfunction "K_2") (pintype "passive"))
      (node (ref "D237") (pin "2") (pinfunction "K_2") (pintype "passive"))
      (node (ref "D238") (pin "2") (pinfunction "K_2") (pintype "passive"))
      (node (ref "D239") (pin "2") (pinfunction "K_2") (pintype "passive"))
      (node (ref "D240") (pin "2") (pinfunction "K_2") (pintype "passive"))
      (node (ref "D241") (pin "2") (pinfunction "K_2") (pintype "passive"))
      (node (ref "D242") (pin "2") (pinfunction "K_2") (pintype "passive"))
    )
    (net (code "18") (name "/row4") (class "Default")
      (node (ref "D243") (pin "2") (pinfunction "K_2") (pintype "passive"))
      (node (ref "D244") (pin "2") (pinfunction "K_2") (pintype "passive"))
      (node (ref "D245") (pin "2") (pinfunction "K_2") (pintype "passive"))
      (node (ref "D246") (pin "2") (pinfunction "K_2") (pintype "passive"))
      (node (ref "D247") (pin "2") (pinfunction "K_2") (pintype "passive"))
      (node (ref "D248") (pin "2") (pinfunction "K_2") (pintype "passive"))
      (node (ref "D249") (pin "2") (pinfunction "K_2") (pintype "passive"))
      (node (ref "D250") (pin "2") (pinfunction "K_2") (pintype "passive"))
      (node (ref "D251") (pin "2") (pinfunction "K_2") (pintype "passive"))
      (node (ref "D252") (pin "2") (pinfunction "K_2") (pintype "passive"))
      (node (ref "D253") (pin "2") (pinfunction "K_2") (pintype "passive"))
      (node (ref "D254") (pin "2") (pinfunction "K_2") (pintype "passive"))
      (node (ref "D255") (pin "2") (pinfunction "K_2") (pintype "passive"))
      (node (ref "D256") (pin "2") (pinfunction "K_2") (pintype "passive"))
    )
    (net (code "19") (name "/row5") (class "Default")
      (node (ref "D257") (pin "2") (pinfunction "K_2") (pintype "passive"))
      (node (ref "D258") (pin "2") (pinfunction "K_2") (pintype "passive"))
      (node (ref "D260") (pin "2") (pinfunction "K_2") (pintype "passive"))
      (node (ref "D261") (pin "2") (pinfunction "K_2") (pintype "passive"))
      (node (ref "D262") (pin "2") (pinfunction "K_2") (pintype "passive"))
      (node (ref "D263") (pin "2") (pinfunction "K_2") (pintype "passive"))
      (node (ref "D264") (pin "2") (pinfunction "K_2") (pintype "passive"))
      (node (ref "D265") (pin "2") (pinfunction "K_2") (pintype "passive"))
      (node (ref "D266") (pin "2") (pinfunction "K_2") (pintype "passive"))
    )
    (net (code "20") (name "Net-(D201-A)") (class "Default")
      (node (ref "D201") (pin "1") (pinfunction "A_1") (pintype "passive"))
      (node (ref "S201") (pin "1") (pinfunction "1_1") (pintype "passive"))
    )
    (net (code "21") (name "Net-(D202-A)") (class "Default")
      (node (ref "D202") (pin "1") (pinfunction "A_1") (pintype "passive"))
      (node (ref "S202") (pin "1") (pinfunction "1_1") (pintype "passive"))
    )
    (net (code "22") (name "Net-(D203-A)") (class "Default")
      (node (ref "D203") (pin "1") (pinfunction "A_1") (pintype "passive"))
      (node (ref "S203") (pin "1") (pinfunction "1_1") (pintype "passive"))
    )
    (net (code "23") (name "Net-(D204-A)") (class "Default")
      (node (ref "D204") (pin "1") (pinfunction "A_1") (pintype "passive"))
      (node (ref "S204") (pin "1") (pinfunction "1_1") (pintype "passive"))
    )
    (net (code "24") (name "Net-(D205-A)") (class "Default")
      (node (ref "D205") (pin "1") (pinfunction "A_1") (pintype "passive"))
      (node (ref "S205") (pin "1") (pinfunction "1_1") (pintype "passive"))
    )
    (net (code "25") (name "Net-(D206-A)") (class "Default")
      (node (ref "D206") (pin "1") (pinfunction "A_1") (pintype "passive"))
      (node (ref "S206") (pin "1") (pinfunction "1_1") (pintype "passive"))
    )
    (net (code "26") (name "Net-(D207-A)") (class "Default")
      (node (ref "D207") (pin "1") (pinfunction "A_1") (pintype "passive"))
      (node (ref "S207") (pin "1") (pinfunction "1_1") (pintype "passive"))
    )
    (net (code "27") (name "Net-(D208-A)") (class "Default")
      (node (ref "D208") (pin "1") (pinfunction "A_1") (pintype "passive"))
      (node (ref "S208") (pin "1") (pinfunction "1_1") (pintype "passive"))
    )
    (net (code "28") (name "Net-(D209-A)") (class "Default")
      (node (ref "D209") (pin "1") (pinfunction "A_1") (pintype "passive"))
      (node (ref "S209") (pin "1") (pinfunction "1_1") (pintype "passive"))
    )
    (net (code "29") (name "Net-(D210-A)") (class "Default")
      (node (ref "D210") (pin "1") (pinfunction "A_1") (pintype "passive"))
      (node (ref "S210") (pin "1") (pinfunction "1_1") (pintype "passive"))
    )
    (net (code "30") (name "Net-(D211-A)") (class "Default")
      (node (ref "D211") (pin "1") (pinfunction "A_1") (pintype "passive"))
      (node (ref "S211") (pin "1") (pinfunction "1_1") (pintype "passive"))
    )
    (net (code "31") (name "Net-(D212-A)") (class "Default")
      (node (ref "D212") (pin "1") (pinfunction "A_1") (pintype "passive"))
      (node (ref "S212") (pin "1") (pinfunction "1_1") (pintype "passive"))
    )
    (net (code "32") (name "Net-(D213-A)") (class "Default")
      (node (ref "D213") (pin "1") (pinfunction "A_1") (pintype "passive"))
      (node (ref "S213") (pin "1") (pinfunction "1_1") (pintype "passive"))
    )
    (net (code "33") (name "Net-(D214-A)") (class "Default")
      (node (ref "D214") (pin "1") (pinfunction "A_1") (pintype "passive"))
      (node (ref "S214") (pin "2") (pinfunction "2_2") (pintype "passive"))
    )
    (net (code "34") (name "Net-(D215-A)") (class "Default")
      (node (ref "D215") (pin "1") (pinfunction "A_1") (pintype "passive"))
      (node (ref "S215") (pin "1") (pinfunction "1_1") (pintype "passive"))
    )
    (net (code "35") (name "Net-(D216-A)") (class "Default")
      (node (ref "D216") (pin "1") (pinfunction "A_1") (pintype "passive"))
      (node (ref "S216") (pin "1") (pinfunction "1_1") (pintype "passive"))
    )
    (net (code "36") (name "Net-(D217-A)") (class "Default")
      (node (ref "D217") (pin "1") (pinfunction "A_1") (pintype "passive"))
      (node (ref "S217") (pin "1") (pinfunction "1_1") (pintype "passive"))
    )
    (net (code "37") (name "Net-(D218-A)") (class "Default")
      (node (ref "D218") (pin "1") (pinfunction "A_1") (pintype "passive"))
      (node (ref "S218") (pin "1") (pinfunction "1_1") (pintype "passive"))
    )
    (net (code "38") (name "Net-(D219-A)") (class "Default")
      (node (ref "D219") (pin "1") (pinfunction "A_1") (pintype "passive"))
      (node (ref "S219") (pin "1") (pinfunction "1_1") (pintype "passive"))
    )
    (net (code "39") (name "Net-(D220-A)") (class "Default")
      (node (ref "D220") (pin "1") (pinfunction "A_1") (pintype "passive"))
      (node (ref "S220") (pin "1") (pinfunction "1_1") (pintype "passive"))
    )
    (net (code "40") (name "Net-(D221-A)") (class "Default")
      (node (ref "D221") (pin "1") (pinfunction "A_1") (pintype "passive"))
      (node (ref "S221") (pin "1") (pinfunction "1_1") (pintype "passive"))
    )
    (net (code "41") (name "Net-(D222-A)") (class "Default")
      (node (ref "D222") (pin "1") (pinfunction "A_1") (pintype "passive"))
      (node (ref "S222") (pin "1") (pinfunction "1_1") (pintype "passive"))
    )
    (net (code "42") (name "Net-(D223-A)") (class "Default")
      (node (ref "D223") (pin "1") (pinfunction "A_1") (pintype "passive"))
      (node (ref "S223") (pin "1") (pinfunction "1_1") (pintype "passive"))
    )
    (net (code "43") (name "Net-(D224-A)") (class "Default")
      (node (ref "D224") (pin "1") (pinfunction "A_1") (pintype "passive"))
      (node (ref "S224") (pin "1") (pinfunction "1_1") (pintype "passive"))
    )
    (net (code "44") (name "Net-(D225-A)") (class "Default")
      (node (ref "D225") (pin "1") (pinfunction "A_1") (pintype "passive"))
      (node (ref "S225") (pin "1") (pinfunction "1_1") (pintype "passive"))
    )
    (net (code "45") (name "Net-(D226-A)") (class "Default")
      (node (ref "D226") (pin "1") (pinfunction "A_1") (pintype "passive"))
      (node (ref "S226") (pin "1") (pinfunction "1_1") (pintype "passive"))
    )
    (net (code "46") (name "Net-(D227-A)") (class "Default")
      (node (ref "D227") (pin "1") (pinfunction "A_1") (pintype "passive"))
      (node (ref "S227") (pin "1") (pinfunction "1_1") (pintype "passive"))
    )
    (net (code "47") (name "Net-(D228-A)") (class "Default")
      (node (ref "D228") (pin "1") (pinfunction "A_1") (pintype "passive"))
      (node (ref "S259") (pin "2") (pinfunction "2_2") (pintype "passive"))
      (node (ref "S259_1") (pin "1") (pinfunction "1_1") (pintype "passive"))
    )
    (net (code "48") (name "Net-(D229-A)") (class "Default")
      (node (ref "D229") (pin "1") (pinfunction "A_1") (pintype "passive"))
      (node (ref "S229") (pin "1") (pinfunction "1_1") (pintype "passive"))
      (node (ref "S229_1") (pin "2") (pinfunction "2_2") (pintype "passive"))
    )
    (net (code "49") (name "Net-(D230-A)") (class "Default")
      (node (ref "D230") (pin "1") (pinfunction "A_1") (pintype "passive"))
      (node (ref "S230") (pin "1") (pinfunction "1_1") (pintype "passive"))
    )
    (net (code "50") (name "Net-(D231-A)") (class "Default")
      (node (ref "D231") (pin "1") (pinfunction "A_1") (pintype "passive"))
      (node (ref "S231") (pin "1") (pinfunction "1_1") (pintype "passive"))
    )
    (net (code "51") (name "Net-(D232-A)") (class "Default")
      (node (ref "D232") (pin "1") (pinfunction "A_1") (pintype "passive"))
      (node (ref "S232") (pin "1") (pinfunction "1_1") (pintype "passive"))
    )
    (net (code "52") (name "Net-(D233-A)") (class "Default")
      (node (ref "D233") (pin "1") (pinfunction "A_1") (pintype "passive"))
      (node (ref "S233") (pin "1") (pinfunction "1_1") (pintype "passive"))
    )
    (net (code "53") (name "Net-(D234-A)") (class "Default")
      (node (ref "D234") (pin "1") (pinfunction "A_1") (pintype "passive"))
      (node (ref "S234") (pin "1") (pinfunction "1_1") (pintype "passive"))
    )
    (net (code "54") (name "Net-(D235-A)") (class "Default")
      (node (ref "D235") (pin "1") (pinfunction "A_1") (pintype "passive"))
      (node (ref "S235") (pin "1") (pinfunction "1_1") (pintype "passive"))
    )
    (net (code "55") (name "Net-(D236-A)") (class "Default")
      (node (ref "D236") (pin "1") (pinfunction "A_1") (pintype "passive"))
      (node (ref "S236") (pin "1") (pinfunction "1_1") (pintype "passive"))
    )
    (net (code "56") (name "Net-(D237-A)") (class "Default")
      (node (ref "D237") (pin "1") (pinfunction "A_1") (pintype "passive"))
      (node (ref "S237") (pin "1") (pinfunction "1_1") (pintype "passive"))
    )
    (net (code "57") (name "Net-(D238-A)") (class "Default")
      (node (ref "D238") (pin "1") (pinfunction "A_1") (pintype "passive"))
      (node (ref "S238") (pin "1") (pinfunction "1_1") (pintype "passive"))
    )
    (net (code "58") (name "Net-(D239-A)") (class "Default")
      (node (ref "D239") (pin "1") (pinfunction "A_1") (pintype "passive"))
      (node (ref "S239") (pin "1") (pinfunction "1_1") (pintype "passive"))
    )
    (net (code "59") (name "Net-(D240-A)") (class "Default")
      (node (ref "D240") (pin "1") (pinfunction "A_1") (pintype "passive"))
      (node (ref "S240") (pin "1") (pinfunction "1_1") (pintype "passive"))
    )
    (net (code "60") (name "Net-(D241-A)") (class "Default")
      (node (ref "D241") (pin "1") (pinfunction "A_1") (pintype "passive"))
      (node (ref "S242") (pin "1") (pinfunction "1_1") (pintype "passive"))
    )
    (net (code "61") (name "Net-(D242-A)") (class "Default")
      (node (ref "D242") (pin "1") (pinfunction "A_1") (pintype "passive"))
      (node (ref "S228") (pin "1") (pinfunction "1_1") (pintype "passive"))
    )
    (net (code "62") (name "Net-(D243-A)") (class "Default")
      (node (ref "D243") (pin "1") (pinfunction "A_1") (pintype "passive"))
      (node (ref "S243") (pin "1") (pinfunction "1_1") (pintype "passive"))
    )
    (net (code "63") (name "Net-(D244-A)") (class "Default")
      (node (ref "D244") (pin "1") (pinfunction "A_1") (pintype "passive"))
      (node (ref "S244") (pin "2") (pinfunction "2_2") (pintype "passive"))
    )
    (net (code "64") (name "Net-(D245-A)") (class "Default")
      (node (ref "D245") (pin "1") (pinfunction "A_1") (pintype "passive"))
      (node (ref "S245") (pin "1") (pinfunction "1_1") (pintype "passive"))
    )
    (net (code "65") (name "Net-(D246-A)") (class "Default")
      (node (ref "D246") (pin "1") (pinfunction "A_1") (pintype "passive"))
      (node (ref "S246") (pin "1") (pinfunction "1_1") (pintype "passive"))
    )
    (net (code "66") (name "Net-(D247-A)") (class "Default")
      (node (ref "D247") (pin "1") (pinfunction "A_1") (pintype "passive"))
      (node (ref "S247") (pin "1") (pinfunction "1_1") (pintype "passive"))
    )
    (net (code "67") (name "Net-(D248-A)") (class "Default")
      (node (ref "D248") (pin "1") (pinfunction "A_1") (pintype "passive"))
      (node (ref "S248") (pin "1") (pinfunction "1_1") (pintype "passive"))
    )
    (net (code "68") (name "Net-(D249-A)") (class "Default")
      (node (ref "D249") (pin "1") (pinfunction "A_1") (pintype "passive"))
      (node (ref "S249") (pin "1") (pinfunction "1_1") (pintype "passive"))
    )
    (net (code "69") (name "Net-(D250-A)") (class "Default")
      (node (ref "D250") (pin "1") (pinfunction "A_1") (pintype "passive"))
      (node (ref "S250") (pin "1") (pinfunction "1_1") (pintype "passive"))
    )
    (net (code "70") (name "Net-(D251-A)") (class "Default")
      (node (ref "D251") (pin "1") (pinfunction "A_1") (pintype "passive"))
      (node (ref "S251") (pin "1") (pinfunction "1_1") (pintype "passive"))
    )
    (net (code "71") (name "Net-(D252-A)") (class "Default")
      (node (ref "D252") (pin "1") (pinfunction "A_1") (pintype "passive"))
      (node (ref "S252") (pin "1") (pinfunction "1_1") (pintype "passive"))
    )
    (net (code "72") (name "Net-(D253-A)") (class "Default")
      (node (ref "D253") (pin "1") (pinfunction "A_1") (pintype "passive"))
      (node (ref "S253") (pin "1") (pinfunction "1_1") (pintype "passive"))
    )
    (net (code "73") (name "Net-(D254-A)") (class "Default")
      (node (ref "D254") (pin "1") (pinfunction "A_1") (pintype "passive"))
      (node (ref "S254") (pin "1") (pinfunction "1_1") (pintype "passive"))
    )
    (net (code "74") (name "Net-(D255-A)") (class "Default")
      (node (ref "D255") (pin "1") (pinfunction "A_1") (pintype "passive"))
      (node (ref "S256") (pin "1") (pinfunction "1_1") (pintype "passive"))
    )
    (net (code "75") (name "Net-(D256-A)") (class "Default")
      (node (ref "D256") (pin "1") (pinfunction "A_1") (pintype "passive"))
      (node (ref "S269") (pin "1") (pinfunction "1_1") (pintype "passive"))
    )
    (net (code "76") (name "Net-(D257-A)") (class "Default")
      (node (ref "D257") (pin "1") (pinfunction "A_1") (pintype "passive"))
      (node (ref "S257") (pin "2") (pinfunction "2_2") (pintype "passive"))
    )
    (net (code "77") (name "Net-(D258-A)") (class "Default")
      (node (ref "D258") (pin "1") (pinfunction "A_1") (pintype "passive"))
      (node (ref "S258") (pin "1") (pinfunction "1_1") (pintype "passive"))
    )
    (net (code "78") (name "Net-(D260-A)") (class "Default")
      (node (ref "D260") (pin "1") (pinfunction "A_1") (pintype "passive"))
      (node (ref "S260") (pin "1") (pinfunction "1_1") (pintype "passive"))
    )
    (net (code "79") (name "Net-(D261-A)") (class "Default")
      (node (ref "D261") (pin "1") (pinfunction "A_1") (pintype "passive"))
      (node (ref "S261") (pin "1") (pinfunction "1_1") (pintype "passive"))
    )
    (net (code "80") (name "Net-(D262-A)") (class "Default")
      (node (ref "D262") (pin "1") (pinfunction "A_1") (pintype "passive"))
      (node (ref "S262") (pin "2") (pinfunction "2_2") (pintype "passive"))
    )
    (net (code "81") (name "Net-(D263-A)") (class "Default")
      (node (ref "D263") (pin "1") (pinfunction "A_1") (pintype "passive"))
      (node (ref "S263") (pin "1") (pinfunction "1_1") (pintype "passive"))
    )
    (net (code "82") (name "Net-(D264-A)") (class "Default")
      (node (ref "D264") (pin "1") (pinfunction "A_1") (pintype "passive"))
      (node (ref "S265") (pin "1") (pinfunction "1_1") (pintype "passive"))
    )
    (net (code "83") (name "Net-(D265-A)") (class "Default")
      (node (ref "D265") (pin "1") (pinfunction "A_1") (pintype "passive"))
      (node (ref "S241") (pin "2") (pinfunction "2_2") (pintype "passive"))
    )
    (net (code "84") (name "Net-(D266-A)") (class "Default")
      (node (ref "D266") (pin "1") (pinfunction "A_1") (pintype "passive"))
      (node (ref "S266") (pin "1") (pinfunction "1_1") (pintype "passive"))
    )
    (net (code "85") (name "unconnected-(STAB1-Pad1)") (class "Default")
      (node (ref "STAB1") (pin "1") (pinfunction "1_1") (pintype "passive"))
    )
    (net (code "86") (name "unconnected-(STAB2-Pad1)") (class "Default")
      (node (ref "STAB2") (pin "1") (pinfunction "1_1") (pintype "passive"))
    )
    (net (code "87") (name "unconnected-(STAB3-Pad1)") (class "Default")
      (node (ref "STAB3") (pin "1") (pinfunction "1_1") (pintype "passive"))
    )
    (net (code "88") (name "unconnected-(STAB4-Pad1)") (class "Default")
      (node (ref "STAB4") (pin "1") (pinfunction "1_1") (pintype "passive"))
    )
    (net (code "89") (name "unconnected-(STAB5-Pad1)") (class "Default")
      (node (ref "STAB5") (pin "1") (pinfunction "1_1") (pintype "passive"))
    )
    (net (code "90") (name "unconnected-(STAB6-Pad1)") (class "Default")
      (node (ref "STAB6") (pin "1") (pinfunction "1_1") (pintype "passive"))
    )
  )
)
